# AMC_Connector.net
KiCad netlist of a schematic drawn in Altium Designer
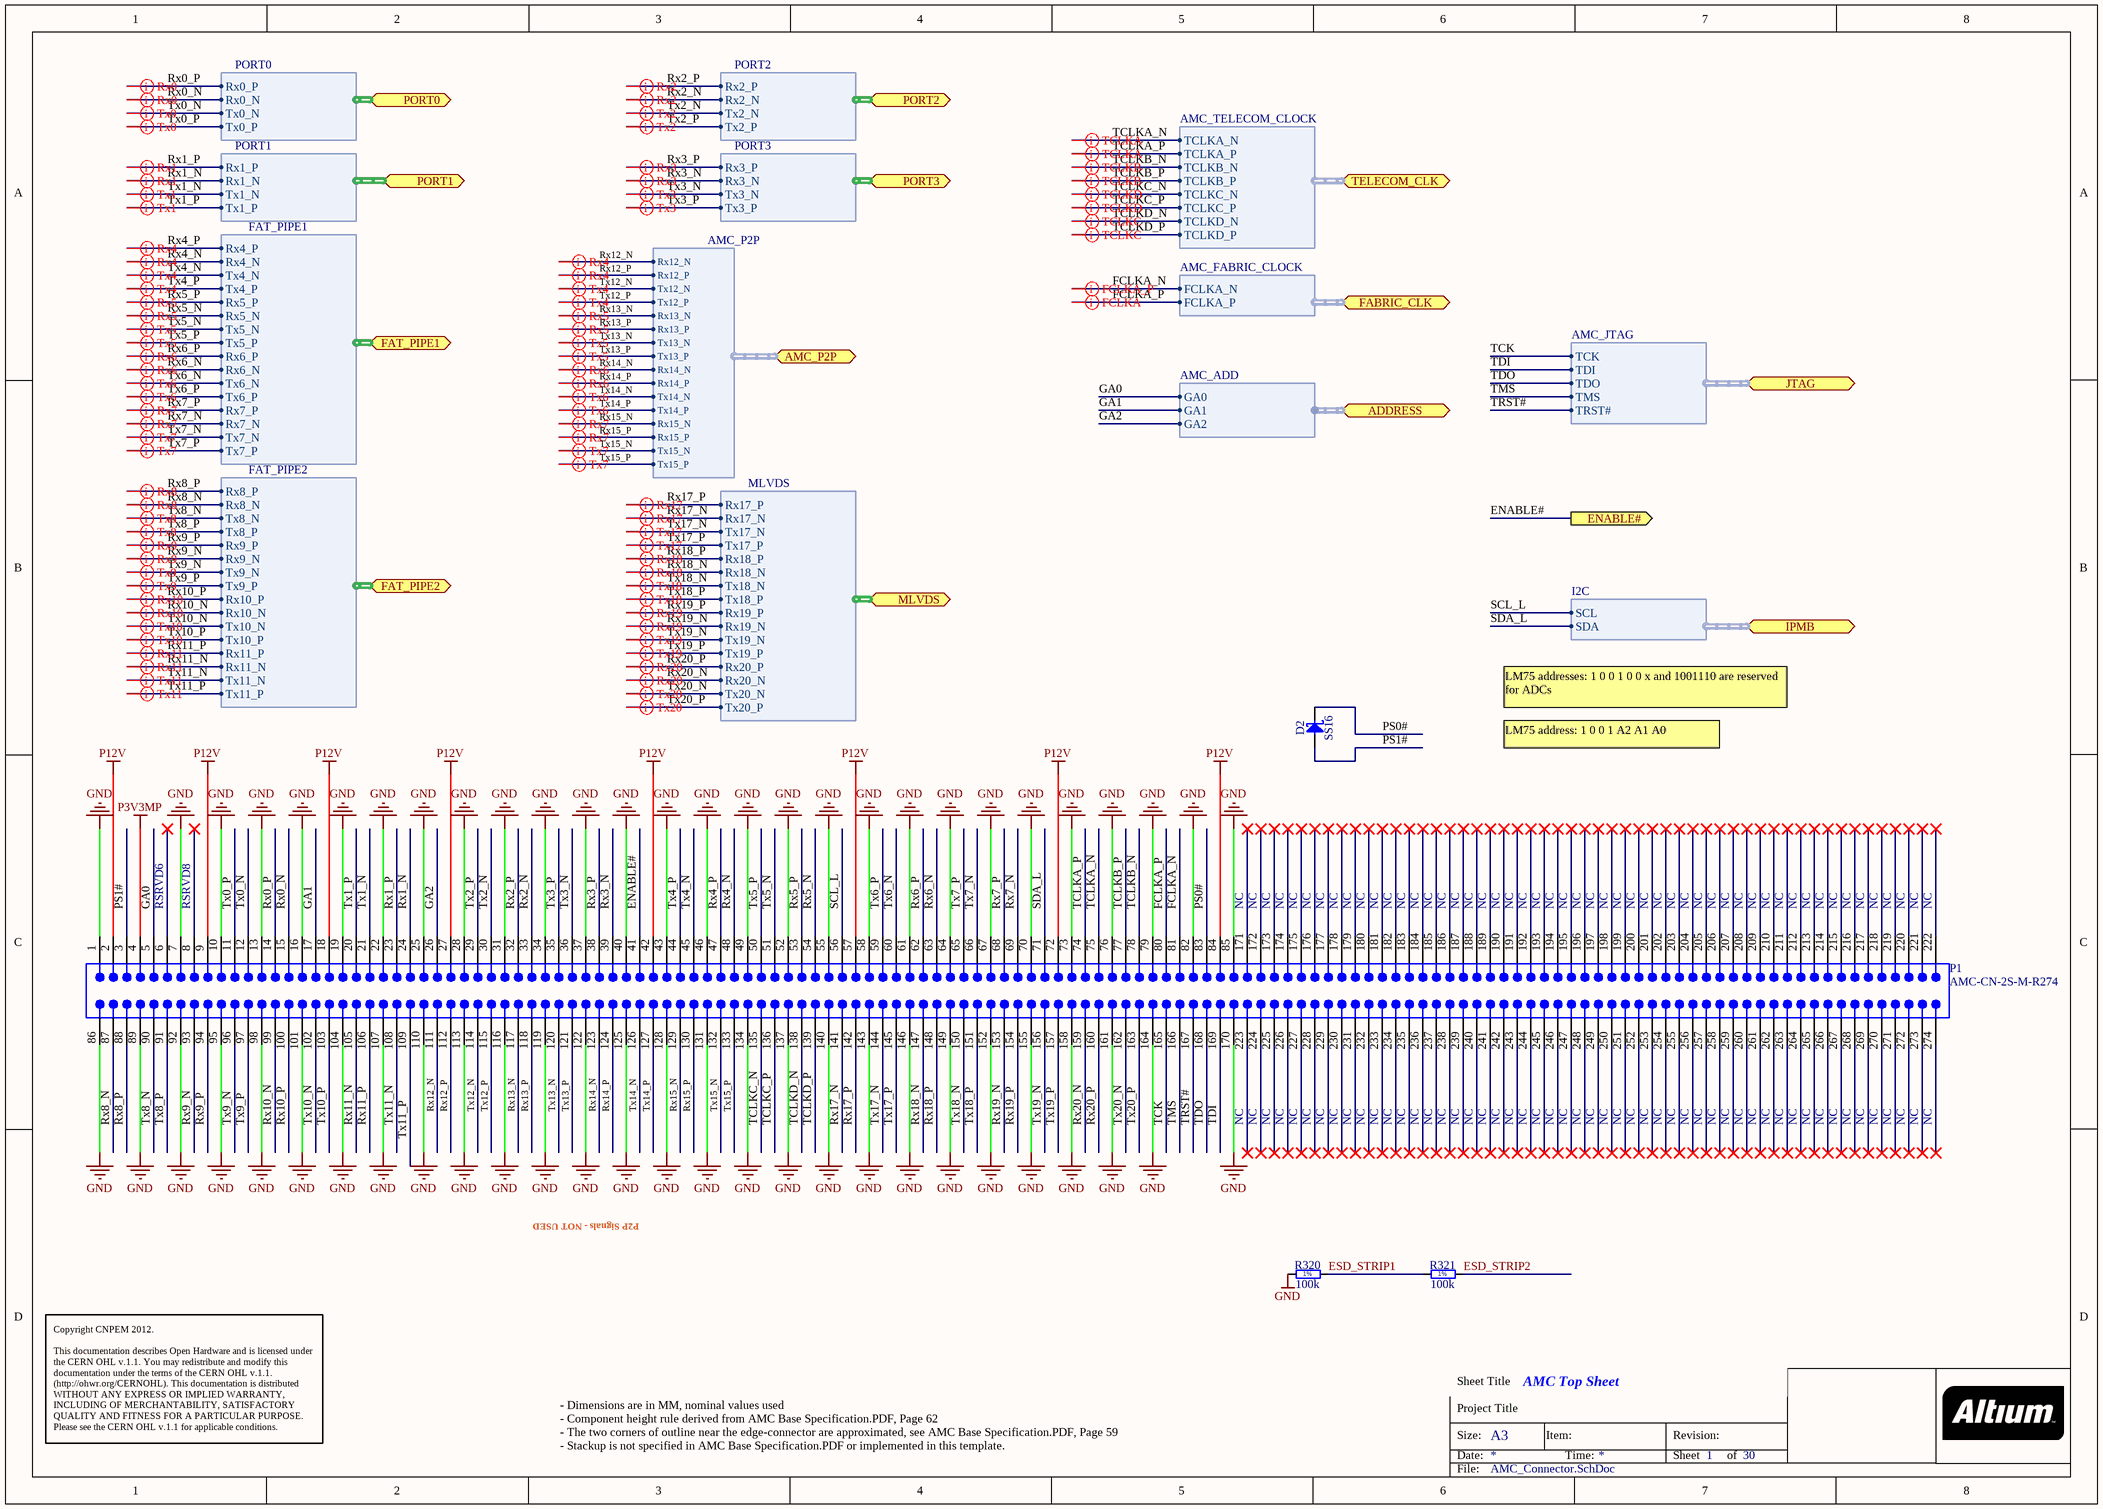
[diagram p0: AMC_Connector.SchDoc]

(export (version "E")
  (design (tool "Eeschema 10.0.6"))
  (components
    (comp (ref "D2")
      (value "SS16")
      (footprint "DIOM5127X229N")
      (description "Schottky Diode")
      (fields
        (field (name "VOLTAGE") "60V")
        (field (name "POWER") "1A")
        (field (name "AUTHOR") "CERN DEM JLC")
      )
      (libsource (lib "ICs And Semiconductors") (part "Diode Schottky"))
    )
    (comp (ref "P1")
      (value "AMC-CN-2S-M-R274")
      (footprint "AMC-GF-2D-750-O274")
      (description "Golden finger, AMC, Dual, Opposite, Pitch 0.75mm, 170-Position")
      (fields (field (name "PUBLISHER") "Altium"))
      (libsource (lib "Altium Shanghai") (part "CMP-0001-00058-2"))
    )
    (comp (ref "R320")
      (value "100k")
      (footprint "RESC3216X65N")
      (description "Resistor - 1%")
      (fields
        (field (name "PART NUMBER") "R1206_100K_1%_0.25W_100PPM")
        (field (name "POWER") "0.25W")
        (field (name "AUTHOR") "CERN DEM JLC")
      )
      (libsource (lib "Resistors") (part "Resistor - 1%"))
    )
    (comp (ref "R321")
      (value "100k")
      (footprint "RESC3216X65N")
      (description "Resistor - 1%")
      (fields
        (field (name "PART NUMBER") "R1206_100K_1%_0.25W_100PPM")
        (field (name "POWER") "0.25W")
        (field (name "AUTHOR") "CERN DEM JLC")
      )
      (libsource (lib "Resistors") (part "Resistor - 1%"))
    )
  )
  (nets
    (net (code "14") (name "/ENABLE#") (class "Default")
      (node (ref "P1") (pin "41") (pinfunction "41_41") (pintype "passive"))
    )
    (net (code "15") (name "/ESD_STRIP1") (class "Default")
      (node (ref "R320") (pin "2") (pinfunction "2_2") (pintype "passive"))
      (node (ref "R321") (pin "1") (pinfunction "1_1") (pintype "passive"))
    )
    (net (code "16") (name "/ESD_STRIP2") (class "Default")
      (node (ref "R321") (pin "2") (pinfunction "2_2") (pintype "passive"))
    )
    (net (code "17") (name "/FCLKA_N") (class "Default")
      (node (ref "P1") (pin "81") (pinfunction "81_81") (pintype "passive"))
    )
    (net (code "18") (name "/FCLKA_P") (class "Default")
      (node (ref "P1") (pin "80") (pinfunction "80_80") (pintype "passive"))
    )
    (net (code "19") (name "/GA0") (class "Default")
      (node (ref "P1") (pin "5") (pinfunction "5_5") (pintype "passive"))
    )
    (net (code "20") (name "/GA1") (class "Default")
      (node (ref "P1") (pin "17") (pinfunction "17_17") (pintype "passive"))
    )
    (net (code "21") (name "/GA2") (class "Default")
      (node (ref "P1") (pin "26") (pinfunction "26_26") (pintype "passive"))
    )
    (net (code "22") (name "/PS0#") (class "Default")
      (node (ref "D2") (pin "1") (pinfunction "C_1") (pintype "passive"))
      (node (ref "P1") (pin "83") (pinfunction "83_83") (pintype "passive"))
    )
    (net (code "23") (name "/PS1#") (class "Default")
      (node (ref "D2") (pin "2") (pinfunction "A_2") (pintype "passive"))
      (node (ref "P1") (pin "3") (pinfunction "3_3") (pintype "passive"))
    )
    (net (code "24") (name "/Rx0_N") (class "Default")
      (node (ref "P1") (pin "15") (pinfunction "15_15") (pintype "passive"))
    )
    (net (code "25") (name "/Rx0_P") (class "Default")
      (node (ref "P1") (pin "14") (pinfunction "14_14") (pintype "passive"))
    )
    (net (code "26") (name "/Rx1_N") (class "Default")
      (node (ref "P1") (pin "24") (pinfunction "24_24") (pintype "passive"))
    )
    (net (code "27") (name "/Rx1_P") (class "Default")
      (node (ref "P1") (pin "23") (pinfunction "23_23") (pintype "passive"))
    )
    (net (code "28") (name "/Rx2_N") (class "Default")
      (node (ref "P1") (pin "33") (pinfunction "33_33") (pintype "passive"))
    )
    (net (code "29") (name "/Rx2_P") (class "Default")
      (node (ref "P1") (pin "32") (pinfunction "32_32") (pintype "passive"))
    )
    (net (code "30") (name "/Rx3_N") (class "Default")
      (node (ref "P1") (pin "39") (pinfunction "39_39") (pintype "passive"))
    )
    (net (code "31") (name "/Rx3_P") (class "Default")
      (node (ref "P1") (pin "38") (pinfunction "38_38") (pintype "passive"))
    )
    (net (code "32") (name "/Rx4_N") (class "Default")
      (node (ref "P1") (pin "48") (pinfunction "48_48") (pintype "passive"))
    )
    (net (code "33") (name "/Rx4_P") (class "Default")
      (node (ref "P1") (pin "47") (pinfunction "47_47") (pintype "passive"))
    )
    (net (code "34") (name "/Rx5_N") (class "Default")
      (node (ref "P1") (pin "54") (pinfunction "54_54") (pintype "passive"))
    )
    (net (code "35") (name "/Rx5_P") (class "Default")
      (node (ref "P1") (pin "53") (pinfunction "53_53") (pintype "passive"))
    )
    (net (code "36") (name "/Rx6_N") (class "Default")
      (node (ref "P1") (pin "63") (pinfunction "63_63") (pintype "passive"))
    )
    (net (code "37") (name "/Rx6_P") (class "Default")
      (node (ref "P1") (pin "62") (pinfunction "62_62") (pintype "passive"))
    )
    (net (code "38") (name "/Rx7_N") (class "Default")
      (node (ref "P1") (pin "69") (pinfunction "69_69") (pintype "passive"))
    )
    (net (code "39") (name "/Rx7_P") (class "Default")
      (node (ref "P1") (pin "68") (pinfunction "68_68") (pintype "passive"))
    )
    (net (code "40") (name "/Rx8_N") (class "Default")
      (node (ref "P1") (pin "87") (pinfunction "87_87") (pintype "passive"))
    )
    (net (code "41") (name "/Rx8_P") (class "Default")
      (node (ref "P1") (pin "88") (pinfunction "88_88") (pintype "passive"))
    )
    (net (code "42") (name "/Rx9_N") (class "Default")
      (node (ref "P1") (pin "93") (pinfunction "93_93") (pintype "passive"))
    )
    (net (code "43") (name "/Rx9_P") (class "Default")
      (node (ref "P1") (pin "94") (pinfunction "94_94") (pintype "passive"))
    )
    (net (code "44") (name "/Rx10_N") (class "Default")
      (node (ref "P1") (pin "99") (pinfunction "99_99") (pintype "passive"))
    )
    (net (code "45") (name "/Rx10_P") (class "Default")
      (node (ref "P1") (pin "100") (pinfunction "100_100") (pintype "passive"))
    )
    (net (code "46") (name "/Rx11_N") (class "Default")
      (node (ref "P1") (pin "105") (pinfunction "105_105") (pintype "passive"))
    )
    (net (code "47") (name "/Rx11_P") (class "Default")
      (node (ref "P1") (pin "106") (pinfunction "106_106") (pintype "passive"))
    )
    (net (code "48") (name "/Rx12_N") (class "Default")
      (node (ref "P1") (pin "111") (pinfunction "111_111") (pintype "passive"))
    )
    (net (code "49") (name "/Rx12_P") (class "Default")
      (node (ref "P1") (pin "112") (pinfunction "112_112") (pintype "passive"))
    )
    (net (code "50") (name "/Rx13_N") (class "Default")
      (node (ref "P1") (pin "117") (pinfunction "117_117") (pintype "passive"))
    )
    (net (code "51") (name "/Rx13_P") (class "Default")
      (node (ref "P1") (pin "118") (pinfunction "118_118") (pintype "passive"))
    )
    (net (code "52") (name "/Rx14_N") (class "Default")
      (node (ref "P1") (pin "123") (pinfunction "123_123") (pintype "passive"))
    )
    (net (code "53") (name "/Rx14_P") (class "Default")
      (node (ref "P1") (pin "124") (pinfunction "124_124") (pintype "passive"))
    )
    (net (code "54") (name "/Rx15_N") (class "Default")
      (node (ref "P1") (pin "129") (pinfunction "129_129") (pintype "passive"))
    )
    (net (code "55") (name "/Rx15_P") (class "Default")
      (node (ref "P1") (pin "130") (pinfunction "130_130") (pintype "passive"))
    )
    (net (code "56") (name "/Rx17_N") (class "Default")
      (node (ref "P1") (pin "141") (pinfunction "141_141") (pintype "passive"))
    )
    (net (code "57") (name "/Rx17_P") (class "Default")
      (node (ref "P1") (pin "142") (pinfunction "142_142") (pintype "passive"))
    )
    (net (code "58") (name "/Rx18_N") (class "Default")
      (node (ref "P1") (pin "147") (pinfunction "147_147") (pintype "passive"))
    )
    (net (code "59") (name "/Rx18_P") (class "Default")
      (node (ref "P1") (pin "148") (pinfunction "148_148") (pintype "passive"))
    )
    (net (code "60") (name "/Rx19_N") (class "Default")
      (node (ref "P1") (pin "153") (pinfunction "153_153") (pintype "passive"))
    )
    (net (code "61") (name "/Rx19_P") (class "Default")
      (node (ref "P1") (pin "154") (pinfunction "154_154") (pintype "passive"))
    )
    (net (code "62") (name "/Rx20_N") (class "Default")
      (node (ref "P1") (pin "159") (pinfunction "159_159") (pintype "passive"))
    )
    (net (code "63") (name "/Rx20_P") (class "Default")
      (node (ref "P1") (pin "160") (pinfunction "160_160") (pintype "passive"))
    )
    (net (code "64") (name "/SCL_L") (class "Default")
      (node (ref "P1") (pin "56") (pinfunction "56_56") (pintype "passive"))
    )
    (net (code "65") (name "/SDA_L") (class "Default")
      (node (ref "P1") (pin "71") (pinfunction "71_71") (pintype "passive"))
    )
    (net (code "66") (name "/TCK") (class "Default")
      (node (ref "P1") (pin "165") (pinfunction "165_165") (pintype "passive"))
    )
    (net (code "67") (name "/TCLKA_N") (class "Default")
      (node (ref "P1") (pin "75") (pinfunction "75_75") (pintype "passive"))
    )
    (net (code "68") (name "/TCLKA_P") (class "Default")
      (node (ref "P1") (pin "74") (pinfunction "74_74") (pintype "passive"))
    )
    (net (code "69") (name "/TCLKB_N") (class "Default")
      (node (ref "P1") (pin "78") (pinfunction "78_78") (pintype "passive"))
    )
    (net (code "70") (name "/TCLKB_P") (class "Default")
      (node (ref "P1") (pin "77") (pinfunction "77_77") (pintype "passive"))
    )
    (net (code "71") (name "/TCLKC_N") (class "Default")
      (node (ref "P1") (pin "135") (pinfunction "135_135") (pintype "passive"))
    )
    (net (code "72") (name "/TCLKC_P") (class "Default")
      (node (ref "P1") (pin "136") (pinfunction "136_136") (pintype "passive"))
    )
    (net (code "73") (name "/TCLKD_N") (class "Default")
      (node (ref "P1") (pin "138") (pinfunction "138_138") (pintype "passive"))
    )
    (net (code "74") (name "/TCLKD_P") (class "Default")
      (node (ref "P1") (pin "139") (pinfunction "139_139") (pintype "passive"))
    )
    (net (code "75") (name "/TDI") (class "Default")
      (node (ref "P1") (pin "169") (pinfunction "169_169") (pintype "passive"))
    )
    (net (code "76") (name "/TDO") (class "Default")
      (node (ref "P1") (pin "168") (pinfunction "168_168") (pintype "passive"))
    )
    (net (code "77") (name "/TMS") (class "Default")
      (node (ref "P1") (pin "166") (pinfunction "166_166") (pintype "passive"))
    )
    (net (code "78") (name "/TRST#") (class "Default")
      (node (ref "P1") (pin "167") (pinfunction "167_167") (pintype "passive"))
    )
    (net (code "79") (name "/Tx0_N") (class "Default")
      (node (ref "P1") (pin "12") (pinfunction "12_12") (pintype "passive"))
    )
    (net (code "80") (name "/Tx0_P") (class "Default")
      (node (ref "P1") (pin "11") (pinfunction "11_11") (pintype "passive"))
    )
    (net (code "81") (name "/Tx1_N") (class "Default")
      (node (ref "P1") (pin "21") (pinfunction "21_21") (pintype "passive"))
    )
    (net (code "82") (name "/Tx1_P") (class "Default")
      (node (ref "P1") (pin "20") (pinfunction "20_20") (pintype "passive"))
    )
    (net (code "83") (name "/Tx2_N") (class "Default")
      (node (ref "P1") (pin "30") (pinfunction "30_30") (pintype "passive"))
    )
    (net (code "84") (name "/Tx2_P") (class "Default")
      (node (ref "P1") (pin "29") (pinfunction "29_29") (pintype "passive"))
    )
    (net (code "85") (name "/Tx3_N") (class "Default")
      (node (ref "P1") (pin "36") (pinfunction "36_36") (pintype "passive"))
    )
    (net (code "86") (name "/Tx3_P") (class "Default")
      (node (ref "P1") (pin "35") (pinfunction "35_35") (pintype "passive"))
    )
    (net (code "87") (name "/Tx4_N") (class "Default")
      (node (ref "P1") (pin "45") (pinfunction "45_45") (pintype "passive"))
    )
    (net (code "88") (name "/Tx4_P") (class "Default")
      (node (ref "P1") (pin "44") (pinfunction "44_44") (pintype "passive"))
    )
    (net (code "89") (name "/Tx5_N") (class "Default")
      (node (ref "P1") (pin "51") (pinfunction "51_51") (pintype "passive"))
    )
    (net (code "90") (name "/Tx5_P") (class "Default")
      (node (ref "P1") (pin "50") (pinfunction "50_50") (pintype "passive"))
    )
    (net (code "91") (name "/Tx6_N") (class "Default")
      (node (ref "P1") (pin "60") (pinfunction "60_60") (pintype "passive"))
    )
    (net (code "92") (name "/Tx6_P") (class "Default")
      (node (ref "P1") (pin "59") (pinfunction "59_59") (pintype "passive"))
    )
    (net (code "93") (name "/Tx7_N") (class "Default")
      (node (ref "P1") (pin "66") (pinfunction "66_66") (pintype "passive"))
    )
    (net (code "94") (name "/Tx7_P") (class "Default")
      (node (ref "P1") (pin "65") (pinfunction "65_65") (pintype "passive"))
    )
    (net (code "95") (name "/Tx8_N") (class "Default")
      (node (ref "P1") (pin "90") (pinfunction "90_90") (pintype "passive"))
    )
    (net (code "96") (name "/Tx8_P") (class "Default")
      (node (ref "P1") (pin "91") (pinfunction "91_91") (pintype "passive"))
    )
    (net (code "97") (name "/Tx9_N") (class "Default")
      (node (ref "P1") (pin "96") (pinfunction "96_96") (pintype "passive"))
    )
    (net (code "98") (name "/Tx9_P") (class "Default")
      (node (ref "P1") (pin "97") (pinfunction "97_97") (pintype "passive"))
    )
    (net (code "99") (name "/Tx10_N") (class "Default")
      (node (ref "P1") (pin "102") (pinfunction "102_102") (pintype "passive"))
    )
    (net (code "100") (name "/Tx10_P") (class "Default")
      (node (ref "P1") (pin "103") (pinfunction "103_103") (pintype "passive"))
    )
    (net (code "101") (name "/Tx11_N") (class "Default")
      (node (ref "P1") (pin "108") (pinfunction "108_108") (pintype "passive"))
    )
    (net (code "102") (name "/Tx11_P") (class "Default")
      (node (ref "P1") (pin "109") (pinfunction "109_109") (pintype "passive"))
    )
    (net (code "103") (name "/Tx12_N") (class "Default")
      (node (ref "P1") (pin "114") (pinfunction "114_114") (pintype "passive"))
    )
    (net (code "104") (name "/Tx12_P") (class "Default")
      (node (ref "P1") (pin "115") (pinfunction "115_115") (pintype "passive"))
    )
    (net (code "105") (name "/Tx13_N") (class "Default")
      (node (ref "P1") (pin "120") (pinfunction "120_120") (pintype "passive"))
    )
    (net (code "106") (name "/Tx13_P") (class "Default")
      (node (ref "P1") (pin "121") (pinfunction "121_121") (pintype "passive"))
    )
    (net (code "107") (name "/Tx14_N") (class "Default")
      (node (ref "P1") (pin "126") (pinfunction "126_126") (pintype "passive"))
    )
    (net (code "108") (name "/Tx14_P") (class "Default")
      (node (ref "P1") (pin "127") (pinfunction "127_127") (pintype "passive"))
    )
    (net (code "109") (name "/Tx15_N") (class "Default")
      (node (ref "P1") (pin "132") (pinfunction "132_132") (pintype "passive"))
    )
    (net (code "110") (name "/Tx15_P") (class "Default")
      (node (ref "P1") (pin "133") (pinfunction "133_133") (pintype "passive"))
    )
    (net (code "111") (name "/Tx17_N") (class "Default")
      (node (ref "P1") (pin "144") (pinfunction "144_144") (pintype "passive"))
    )
    (net (code "112") (name "/Tx17_P") (class "Default")
      (node (ref "P1") (pin "145") (pinfunction "145_145") (pintype "passive"))
    )
    (net (code "113") (name "/Tx18_N") (class "Default")
      (node (ref "P1") (pin "150") (pinfunction "150_150") (pintype "passive"))
    )
    (net (code "114") (name "/Tx18_P") (class "Default")
      (node (ref "P1") (pin "151") (pinfunction "151_151") (pintype "passive"))
    )
    (net (code "115") (name "/Tx19_N") (class "Default")
      (node (ref "P1") (pin "156") (pinfunction "156_156") (pintype "passive"))
    )
    (net (code "116") (name "/Tx19_P") (class "Default")
      (node (ref "P1") (pin "157") (pinfunction "157_157") (pintype "passive"))
    )
    (net (code "117") (name "/Tx20_N") (class "Default")
      (node (ref "P1") (pin "162") (pinfunction "162_162") (pintype "passive"))
    )
    (net (code "118") (name "/Tx20_P") (class "Default")
      (node (ref "P1") (pin "163") (pinfunction "163_163") (pintype "passive"))
    )
    (net (code "132") (name "GND") (class "Default")
      (node (ref "P1") (pin "1") (pinfunction "1_1") (pintype "passive"))
      (node (ref "P1") (pin "10") (pinfunction "10_10") (pintype "passive"))
      (node (ref "P1") (pin "101") (pinfunction "101_101") (pintype "passive"))
      (node (ref "P1") (pin "104") (pinfunction "104_104") (pintype "passive"))
      (node (ref "P1") (pin "107") (pinfunction "107_107") (pintype "passive"))
      (node (ref "P1") (pin "110") (pinfunction "110_110") (pintype "passive"))
      (node (ref "P1") (pin "113") (pinfunction "113_113") (pintype "passive"))
      (node (ref "P1") (pin "116") (pinfunction "116_116") (pintype "passive"))
      (node (ref "P1") (pin "119") (pinfunction "119_119") (pintype "passive"))
      (node (ref "P1") (pin "122") (pinfunction "122_122") (pintype "passive"))
      (node (ref "P1") (pin "125") (pinfunction "125_125") (pintype "passive"))
      (node (ref "P1") (pin "128") (pinfunction "128_128") (pintype "passive"))
      (node (ref "P1") (pin "13") (pinfunction "13_13") (pintype "passive"))
      (node (ref "P1") (pin "131") (pinfunction "131_131") (pintype "passive"))
      (node (ref "P1") (pin "134") (pinfunction "134_134") (pintype "passive"))
      (node (ref "P1") (pin "137") (pinfunction "137_137") (pintype "passive"))
      (node (ref "P1") (pin "140") (pinfunction "140_140") (pintype "passive"))
      (node (ref "P1") (pin "143") (pinfunction "143_143") (pintype "passive"))
      (node (ref "P1") (pin "146") (pinfunction "146_146") (pintype "passive"))
      (node (ref "P1") (pin "149") (pinfunction "149_149") (pintype "passive"))
      (node (ref "P1") (pin "152") (pinfunction "152_152") (pintype "passive"))
      (node (ref "P1") (pin "155") (pinfunction "155_155") (pintype "passive"))
      (node (ref "P1") (pin "158") (pinfunction "158_158") (pintype "passive"))
      (node (ref "P1") (pin "16") (pinfunction "16_16") (pintype "passive"))
      (node (ref "P1") (pin "161") (pinfunction "161_161") (pintype "passive"))
      (node (ref "P1") (pin "164") (pinfunction "164_164") (pintype "passive"))
      (node (ref "P1") (pin "170") (pinfunction "170_170") (pintype "passive"))
      (node (ref "P1") (pin "19") (pinfunction "19_19") (pintype "passive"))
      (node (ref "P1") (pin "22") (pinfunction "22_22") (pintype "passive"))
      (node (ref "P1") (pin "25") (pinfunction "25_25") (pintype "passive"))
      (node (ref "P1") (pin "28") (pinfunction "28_28") (pintype "passive"))
      (node (ref "P1") (pin "31") (pinfunction "31_31") (pintype "passive"))
      (node (ref "P1") (pin "34") (pinfunction "34_34") (pintype "passive"))
      (node (ref "P1") (pin "37") (pinfunction "37_37") (pintype "passive"))
      (node (ref "P1") (pin "40") (pinfunction "40_40") (pintype "passive"))
      (node (ref "P1") (pin "43") (pinfunction "43_43") (pintype "passive"))
      (node (ref "P1") (pin "46") (pinfunction "46_46") (pintype "passive"))
      (node (ref "P1") (pin "49") (pinfunction "49_49") (pintype "passive"))
      (node (ref "P1") (pin "52") (pinfunction "52_52") (pintype "passive"))
      (node (ref "P1") (pin "55") (pinfunction "55_55") (pintype "passive"))
      (node (ref "P1") (pin "58") (pinfunction "58_58") (pintype "passive"))
      (node (ref "P1") (pin "61") (pinfunction "61_61") (pintype "passive"))
      (node (ref "P1") (pin "64") (pinfunction "64_64") (pintype "passive"))
      (node (ref "P1") (pin "67") (pinfunction "67_67") (pintype "passive"))
      (node (ref "P1") (pin "7") (pinfunction "7_7") (pintype "passive"))
      (node (ref "P1") (pin "70") (pinfunction "70_70") (pintype "passive"))
      (node (ref "P1") (pin "73") (pinfunction "73_73") (pintype "passive"))
      (node (ref "P1") (pin "76") (pinfunction "76_76") (pintype "passive"))
      (node (ref "P1") (pin "79") (pinfunction "79_79") (pintype "passive"))
      (node (ref "P1") (pin "82") (pinfunction "82_82") (pintype "passive"))
      (node (ref "P1") (pin "85") (pinfunction "85_85") (pintype "passive"))
      (node (ref "P1") (pin "86") (pinfunction "86_86") (pintype "passive"))
      (node (ref "P1") (pin "89") (pinfunction "89_89") (pintype "passive"))
      (node (ref "P1") (pin "92") (pinfunction "92_92") (pintype "passive"))
      (node (ref "P1") (pin "95") (pinfunction "95_95") (pintype "passive"))
      (node (ref "P1") (pin "98") (pinfunction "98_98") (pintype "passive"))
      (node (ref "R320") (pin "1") (pinfunction "1_1") (pintype "passive"))
    )
    (net (code "133") (name "P3V3MP") (class "Default")
      (node (ref "P1") (pin "4") (pinfunction "4_4") (pintype "passive"))
    )
    (net (code "134") (name "P12V") (class "Default")
      (node (ref "P1") (pin "18") (pinfunction "18_18") (pintype "passive"))
      (node (ref "P1") (pin "2") (pinfunction "2_2") (pintype "passive"))
      (node (ref "P1") (pin "27") (pinfunction "27_27") (pintype "passive"))
      (node (ref "P1") (pin "42") (pinfunction "42_42") (pintype "passive"))
      (node (ref "P1") (pin "57") (pinfunction "57_57") (pintype "passive"))
      (node (ref "P1") (pin "72") (pinfunction "72_72") (pintype "passive"))
      (node (ref "P1") (pin "84") (pinfunction "84_84") (pintype "passive"))
      (node (ref "P1") (pin "9") (pinfunction "9_9") (pintype "passive"))
    )
    (net (code "135") (name "unconnected-(P1-Pad6)") (class "Default")
      (node (ref "P1") (pin "6") (pinfunction "6_6") (pintype "passive+no_connect"))
    )
    (net (code "136") (name "unconnected-(P1-Pad8)") (class "Default")
      (node (ref "P1") (pin "8") (pinfunction "8_8") (pintype "passive+no_connect"))
    )
    (net (code "137") (name "unconnected-(P1-Pad171)") (class "Default")
      (node (ref "P1") (pin "171") (pinfunction "171_171") (pintype "passive+no_connect"))
    )
    (net (code "138") (name "unconnected-(P1-Pad172)") (class "Default")
      (node (ref "P1") (pin "172") (pinfunction "172_172") (pintype "passive+no_connect"))
    )
    (net (code "139") (name "unconnected-(P1-Pad173)") (class "Default")
      (node (ref "P1") (pin "173") (pinfunction "173_173") (pintype "passive+no_connect"))
    )
    (net (code "140") (name "unconnected-(P1-Pad174)") (class "Default")
      (node (ref "P1") (pin "174") (pinfunction "174_174") (pintype "passive+no_connect"))
    )
    (net (code "141") (name "unconnected-(P1-Pad175)") (class "Default")
      (node (ref "P1") (pin "175") (pinfunction "175_175") (pintype "passive+no_connect"))
    )
    (net (code "142") (name "unconnected-(P1-Pad176)") (class "Default")
      (node (ref "P1") (pin "176") (pinfunction "176_176") (pintype "passive+no_connect"))
    )
    (net (code "143") (name "unconnected-(P1-Pad177)") (class "Default")
      (node (ref "P1") (pin "177") (pinfunction "177_177") (pintype "passive+no_connect"))
    )
    (net (code "144") (name "unconnected-(P1-Pad178)") (class "Default")
      (node (ref "P1") (pin "178") (pinfunction "178_178") (pintype "passive+no_connect"))
    )
    (net (code "145") (name "unconnected-(P1-Pad179)") (class "Default")
      (node (ref "P1") (pin "179") (pinfunction "179_179") (pintype "passive+no_connect"))
    )
    (net (code "146") (name "unconnected-(P1-Pad180)") (class "Default")
      (node (ref "P1") (pin "180") (pinfunction "180_180") (pintype "passive+no_connect"))
    )
    (net (code "147") (name "unconnected-(P1-Pad181)") (class "Default")
      (node (ref "P1") (pin "181") (pinfunction "181_181") (pintype "passive+no_connect"))
    )
    (net (code "148") (name "unconnected-(P1-Pad182)") (class "Default")
      (node (ref "P1") (pin "182") (pinfunction "182_182") (pintype "passive+no_connect"))
    )
    (net (code "149") (name "unconnected-(P1-Pad183)") (class "Default")
      (node (ref "P1") (pin "183") (pinfunction "183_183") (pintype "passive+no_connect"))
    )
    (net (code "150") (name "unconnected-(P1-Pad184)") (class "Default")
      (node (ref "P1") (pin "184") (pinfunction "184_184") (pintype "passive+no_connect"))
    )
    (net (code "151") (name "unconnected-(P1-Pad185)") (class "Default")
      (node (ref "P1") (pin "185") (pinfunction "185_185") (pintype "passive+no_connect"))
    )
    (net (code "152") (name "unconnected-(P1-Pad186)") (class "Default")
      (node (ref "P1") (pin "186") (pinfunction "186_186") (pintype "passive+no_connect"))
    )
    (net (code "153") (name "unconnected-(P1-Pad187)") (class "Default")
      (node (ref "P1") (pin "187") (pinfunction "187_187") (pintype "passive+no_connect"))
    )
    (net (code "154") (name "unconnected-(P1-Pad188)") (class "Default")
      (node (ref "P1") (pin "188") (pinfunction "188_188") (pintype "passive+no_connect"))
    )
    (net (code "155") (name "unconnected-(P1-Pad189)") (class "Default")
      (node (ref "P1") (pin "189") (pinfunction "189_189") (pintype "passive+no_connect"))
    )
    (net (code "156") (name "unconnected-(P1-Pad190)") (class "Default")
      (node (ref "P1") (pin "190") (pinfunction "190_190") (pintype "passive+no_connect"))
    )
    (net (code "157") (name "unconnected-(P1-Pad191)") (class "Default")
      (node (ref "P1") (pin "191") (pinfunction "191_191") (pintype "passive+no_connect"))
    )
    (net (code "158") (name "unconnected-(P1-Pad192)") (class "Default")
      (node (ref "P1") (pin "192") (pinfunction "192_192") (pintype "passive+no_connect"))
    )
    (net (code "159") (name "unconnected-(P1-Pad193)") (class "Default")
      (node (ref "P1") (pin "193") (pinfunction "193_193") (pintype "passive+no_connect"))
    )
    (net (code "160") (name "unconnected-(P1-Pad194)") (class "Default")
      (node (ref "P1") (pin "194") (pinfunction "194_194") (pintype "passive+no_connect"))
    )
    (net (code "161") (name "unconnected-(P1-Pad195)") (class "Default")
      (node (ref "P1") (pin "195") (pinfunction "195_195") (pintype "passive+no_connect"))
    )
    (net (code "162") (name "unconnected-(P1-Pad196)") (class "Default")
      (node (ref "P1") (pin "196") (pinfunction "196_196") (pintype "passive+no_connect"))
    )
    (net (code "163") (name "unconnected-(P1-Pad197)") (class "Default")
      (node (ref "P1") (pin "197") (pinfunction "197_197") (pintype "passive+no_connect"))
    )
    (net (code "164") (name "unconnected-(P1-Pad198)") (class "Default")
      (node (ref "P1") (pin "198") (pinfunction "198_198") (pintype "passive+no_connect"))
    )
    (net (code "165") (name "unconnected-(P1-Pad199)") (class "Default")
      (node (ref "P1") (pin "199") (pinfunction "199_199") (pintype "passive+no_connect"))
    )
    (net (code "166") (name "unconnected-(P1-Pad200)") (class "Default")
      (node (ref "P1") (pin "200") (pinfunction "200_200") (pintype "passive+no_connect"))
    )
    (net (code "167") (name "unconnected-(P1-Pad201)") (class "Default")
      (node (ref "P1") (pin "201") (pinfunction "201_201") (pintype "passive+no_connect"))
    )
    (net (code "168") (name "unconnected-(P1-Pad202)") (class "Default")
      (node (ref "P1") (pin "202") (pinfunction "202_202") (pintype "passive+no_connect"))
    )
    (net (code "169") (name "unconnected-(P1-Pad203)") (class "Default")
      (node (ref "P1") (pin "203") (pinfunction "203_203") (pintype "passive+no_connect"))
    )
    (net (code "170") (name "unconnected-(P1-Pad204)") (class "Default")
      (node (ref "P1") (pin "204") (pinfunction "204_204") (pintype "passive+no_connect"))
    )
    (net (code "171") (name "unconnected-(P1-Pad205)") (class "Default")
      (node (ref "P1") (pin "205") (pinfunction "205_205") (pintype "passive+no_connect"))
    )
    (net (code "172") (name "unconnected-(P1-Pad206)") (class "Default")
      (node (ref "P1") (pin "206") (pinfunction "206_206") (pintype "passive+no_connect"))
    )
    (net (code "173") (name "unconnected-(P1-Pad207)") (class "Default")
      (node (ref "P1") (pin "207") (pinfunction "207_207") (pintype "passive+no_connect"))
    )
    (net (code "174") (name "unconnected-(P1-Pad208)") (class "Default")
      (node (ref "P1") (pin "208") (pinfunction "208_208") (pintype "passive+no_connect"))
    )
    (net (code "175") (name "unconnected-(P1-Pad209)") (class "Default")
      (node (ref "P1") (pin "209") (pinfunction "209_209") (pintype "passive+no_connect"))
    )
    (net (code "176") (name "unconnected-(P1-Pad210)") (class "Default")
      (node (ref "P1") (pin "210") (pinfunction "210_210") (pintype "passive+no_connect"))
    )
    (net (code "177") (name "unconnected-(P1-Pad211)") (class "Default")
      (node (ref "P1") (pin "211") (pinfunction "211_211") (pintype "passive+no_connect"))
    )
    (net (code "178") (name "unconnected-(P1-Pad212)") (class "Default")
      (node (ref "P1") (pin "212") (pinfunction "212_212") (pintype "passive+no_connect"))
    )
    (net (code "179") (name "unconnected-(P1-Pad213)") (class "Default")
      (node (ref "P1") (pin "213") (pinfunction "213_213") (pintype "passive+no_connect"))
    )
    (net (code "180") (name "unconnected-(P1-Pad214)") (class "Default")
      (node (ref "P1") (pin "214") (pinfunction "214_214") (pintype "passive+no_connect"))
    )
    (net (code "181") (name "unconnected-(P1-Pad215)") (class "Default")
      (node (ref "P1") (pin "215") (pinfunction "215_215") (pintype "passive+no_connect"))
    )
    (net (code "182") (name "unconnected-(P1-Pad216)") (class "Default")
      (node (ref "P1") (pin "216") (pinfunction "216_216") (pintype "passive+no_connect"))
    )
    (net (code "183") (name "unconnected-(P1-Pad217)") (class "Default")
      (node (ref "P1") (pin "217") (pinfunction "217_217") (pintype "passive+no_connect"))
    )
    (net (code "184") (name "unconnected-(P1-Pad218)") (class "Default")
      (node (ref "P1") (pin "218") (pinfunction "218_218") (pintype "passive+no_connect"))
    )
    (net (code "185") (name "unconnected-(P1-Pad219)") (class "Default")
      (node (ref "P1") (pin "219") (pinfunction "219_219") (pintype "passive+no_connect"))
    )
    (net (code "186") (name "unconnected-(P1-Pad220)") (class "Default")
      (node (ref "P1") (pin "220") (pinfunction "220_220") (pintype "passive+no_connect"))
    )
    (net (code "187") (name "unconnected-(P1-Pad221)") (class "Default")
      (node (ref "P1") (pin "221") (pinfunction "221_221") (pintype "passive+no_connect"))
    )
    (net (code "188") (name "unconnected-(P1-Pad222)") (class "Default")
      (node (ref "P1") (pin "222") (pinfunction "222_222") (pintype "passive+no_connect"))
    )
    (net (code "189") (name "unconnected-(P1-Pad223)") (class "Default")
      (node (ref "P1") (pin "223") (pinfunction "223_223") (pintype "passive+no_connect"))
    )
    (net (code "190") (name "unconnected-(P1-Pad224)") (class "Default")
      (node (ref "P1") (pin "224") (pinfunction "224_224") (pintype "passive+no_connect"))
    )
    (net (code "191") (name "unconnected-(P1-Pad225)") (class "Default")
      (node (ref "P1") (pin "225") (pinfunction "225_225") (pintype "passive+no_connect"))
    )
    (net (code "192") (name "unconnected-(P1-Pad226)") (class "Default")
      (node (ref "P1") (pin "226") (pinfunction "226_226") (pintype "passive+no_connect"))
    )
    (net (code "193") (name "unconnected-(P1-Pad227)") (class "Default")
      (node (ref "P1") (pin "227") (pinfunction "227_227") (pintype "passive+no_connect"))
    )
    (net (code "194") (name "unconnected-(P1-Pad228)") (class "Default")
      (node (ref "P1") (pin "228") (pinfunction "228_228") (pintype "passive+no_connect"))
    )
    (net (code "195") (name "unconnected-(P1-Pad229)") (class "Default")
      (node (ref "P1") (pin "229") (pinfunction "229_229") (pintype "passive+no_connect"))
    )
    (net (code "196") (name "unconnected-(P1-Pad230)") (class "Default")
      (node (ref "P1") (pin "230") (pinfunction "230_230") (pintype "passive+no_connect"))
    )
    (net (code "197") (name "unconnected-(P1-Pad231)") (class "Default")
      (node (ref "P1") (pin "231") (pinfunction "231_231") (pintype "passive+no_connect"))
    )
    (net (code "198") (name "unconnected-(P1-Pad232)") (class "Default")
      (node (ref "P1") (pin "232") (pinfunction "232_232") (pintype "passive+no_connect"))
    )
    (net (code "199") (name "unconnected-(P1-Pad233)") (class "Default")
      (node (ref "P1") (pin "233") (pinfunction "233_233") (pintype "passive+no_connect"))
    )
    (net (code "200") (name "unconnected-(P1-Pad234)") (class "Default")
      (node (ref "P1") (pin "234") (pinfunction "234_234") (pintype "passive+no_connect"))
    )
    (net (code "201") (name "unconnected-(P1-Pad235)") (class "Default")
      (node (ref "P1") (pin "235") (pinfunction "235_235") (pintype "passive+no_connect"))
    )
    (net (code "202") (name "unconnected-(P1-Pad236)") (class "Default")
      (node (ref "P1") (pin "236") (pinfunction "236_236") (pintype "passive+no_connect"))
    )
    (net (code "203") (name "unconnected-(P1-Pad237)") (class "Default")
      (node (ref "P1") (pin "237") (pinfunction "237_237") (pintype "passive+no_connect"))
    )
    (net (code "204") (name "unconnected-(P1-Pad238)") (class "Default")
      (node (ref "P1") (pin "238") (pinfunction "238_238") (pintype "passive+no_connect"))
    )
    (net (code "205") (name "unconnected-(P1-Pad239)") (class "Default")
      (node (ref "P1") (pin "239") (pinfunction "239_239") (pintype "passive+no_connect"))
    )
    (net (code "206") (name "unconnected-(P1-Pad240)") (class "Default")
      (node (ref "P1") (pin "240") (pinfunction "240_240") (pintype "passive+no_connect"))
    )
    (net (code "207") (name "unconnected-(P1-Pad241)") (class "Default")
      (node (ref "P1") (pin "241") (pinfunction "241_241") (pintype "passive+no_connect"))
    )
    (net (code "208") (name "unconnected-(P1-Pad242)") (class "Default")
      (node (ref "P1") (pin "242") (pinfunction "242_242") (pintype "passive+no_connect"))
    )
    (net (code "209") (name "unconnected-(P1-Pad243)") (class "Default")
      (node (ref "P1") (pin "243") (pinfunction "243_243") (pintype "passive+no_connect"))
    )
    (net (code "210") (name "unconnected-(P1-Pad244)") (class "Default")
      (node (ref "P1") (pin "244") (pinfunction "244_244") (pintype "passive+no_connect"))
    )
    (net (code "211") (name "unconnected-(P1-Pad245)") (class "Default")
      (node (ref "P1") (pin "245") (pinfunction "245_245") (pintype "passive+no_connect"))
    )
    (net (code "212") (name "unconnected-(P1-Pad246)") (class "Default")
      (node (ref "P1") (pin "246") (pinfunction "246_246") (pintype "passive+no_connect"))
    )
    (net (code "213") (name "unconnected-(P1-Pad247)") (class "Default")
      (node (ref "P1") (pin "247") (pinfunction "247_247") (pintype "passive+no_connect"))
    )
    (net (code "214") (name "unconnected-(P1-Pad248)") (class "Default")
      (node (ref "P1") (pin "248") (pinfunction "248_248") (pintype "passive+no_connect"))
    )
    (net (code "215") (name "unconnected-(P1-Pad249)") (class "Default")
      (node (ref "P1") (pin "249") (pinfunction "249_249") (pintype "passive+no_connect"))
    )
    (net (code "216") (name "unconnected-(P1-Pad250)") (class "Default")
      (node (ref "P1") (pin "250") (pinfunction "250_250") (pintype "passive+no_connect"))
    )
    (net (code "217") (name "unconnected-(P1-Pad251)") (class "Default")
      (node (ref "P1") (pin "251") (pinfunction "251_251") (pintype "passive+no_connect"))
    )
    (net (code "218") (name "unconnected-(P1-Pad252)") (class "Default")
      (node (ref "P1") (pin "252") (pinfunction "252_252") (pintype "passive+no_connect"))
    )
    (net (code "219") (name "unconnected-(P1-Pad253)") (class "Default")
      (node (ref "P1") (pin "253") (pinfunction "253_253") (pintype "passive+no_connect"))
    )
    (net (code "220") (name "unconnected-(P1-Pad254)") (class "Default")
      (node (ref "P1") (pin "254") (pinfunction "254_254") (pintype "passive+no_connect"))
    )
    (net (code "221") (name "unconnected-(P1-Pad255)") (class "Default")
      (node (ref "P1") (pin "255") (pinfunction "255_255") (pintype "passive+no_connect"))
    )
    (net (code "222") (name "unconnected-(P1-Pad256)") (class "Default")
      (node (ref "P1") (pin "256") (pinfunction "256_256") (pintype "passive+no_connect"))
    )
    (net (code "223") (name "unconnected-(P1-Pad257)") (class "Default")
      (node (ref "P1") (pin "257") (pinfunction "257_257") (pintype "passive+no_connect"))
    )
    (net (code "224") (name "unconnected-(P1-Pad258)") (class "Default")
      (node (ref "P1") (pin "258") (pinfunction "258_258") (pintype "passive+no_connect"))
    )
    (net (code "225") (name "unconnected-(P1-Pad259)") (class "Default")
      (node (ref "P1") (pin "259") (pinfunction "259_259") (pintype "passive+no_connect"))
    )
    (net (code "226") (name "unconnected-(P1-Pad260)") (class "Default")
      (node (ref "P1") (pin "260") (pinfunction "260_260") (pintype "passive+no_connect"))
    )
    (net (code "227") (name "unconnected-(P1-Pad261)") (class "Default")
      (node (ref "P1") (pin "261") (pinfunction "261_261") (pintype "passive+no_connect"))
    )
    (net (code "228") (name "unconnected-(P1-Pad262)") (class "Default")
      (node (ref "P1") (pin "262") (pinfunction "262_262") (pintype "passive+no_connect"))
    )
    (net (code "229") (name "unconnected-(P1-Pad263)") (class "Default")
      (node (ref "P1") (pin "263") (pinfunction "263_263") (pintype "passive+no_connect"))
    )
    (net (code "230") (name "unconnected-(P1-Pad264)") (class "Default")
      (node (ref "P1") (pin "264") (pinfunction "264_264") (pintype "passive+no_connect"))
    )
    (net (code "231") (name "unconnected-(P1-Pad265)") (class "Default")
      (node (ref "P1") (pin "265") (pinfunction "265_265") (pintype "passive+no_connect"))
    )
    (net (code "232") (name "unconnected-(P1-Pad266)") (class "Default")
      (node (ref "P1") (pin "266") (pinfunction "266_266") (pintype "passive+no_connect"))
    )
    (net (code "233") (name "unconnected-(P1-Pad267)") (class "Default")
      (node (ref "P1") (pin "267") (pinfunction "267_267") (pintype "passive+no_connect"))
    )
    (net (code "234") (name "unconnected-(P1-Pad268)") (class "Default")
      (node (ref "P1") (pin "268") (pinfunction "268_268") (pintype "passive+no_connect"))
    )
    (net (code "235") (name "unconnected-(P1-Pad269)") (class "Default")
      (node (ref "P1") (pin "269") (pinfunction "269_269") (pintype "passive+no_connect"))
    )
    (net (code "236") (name "unconnected-(P1-Pad270)") (class "Default")
      (node (ref "P1") (pin "270") (pinfunction "270_270") (pintype "passive+no_connect"))
    )
    (net (code "237") (name "unconnected-(P1-Pad271)") (class "Default")
      (node (ref "P1") (pin "271") (pinfunction "271_271") (pintype "passive+no_connect"))
    )
    (net (code "238") (name "unconnected-(P1-Pad272)") (class "Default")
      (node (ref "P1") (pin "272") (pinfunction "272_272") (pintype "passive+no_connect"))
    )
    (net (code "239") (name "unconnected-(P1-Pad273)") (class "Default")
      (node (ref "P1") (pin "273") (pinfunction "273_273") (pintype "passive+no_connect"))
    )
    (net (code "240") (name "unconnected-(P1-Pad274)") (class "Default")
      (node (ref "P1") (pin "274") (pinfunction "274_274") (pintype "passive+no_connect"))
    )
  )
)
